# USB_HUB_V1_2.net
KiCad netlist of a schematic drawn in Altium Designer
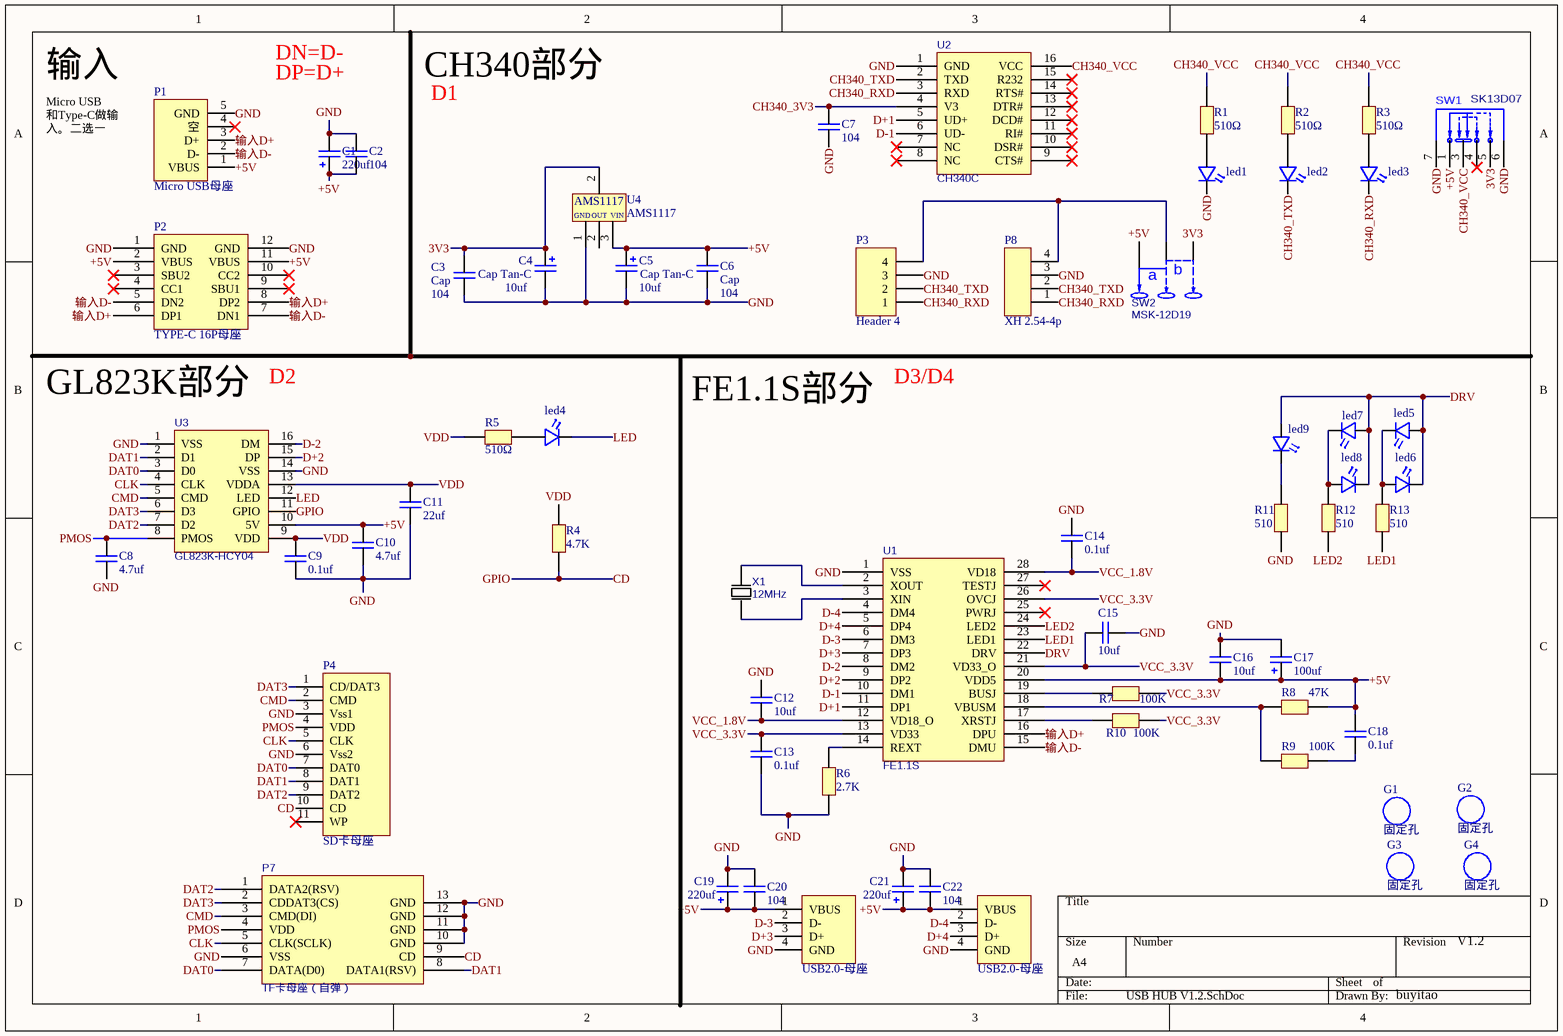
[diagram p0: USB HUB V1.2.SchDoc]

(export (version "E")
  (design (tool "Eeschema 10.0.6"))
  (components
    (comp (ref "C1")
      (value "220uf")
      (footprint "CAP-SMD_BD6.3-L6.6-W6.6-FD")
      (libsource (lib "电容") (part "pcap"))
    )
    (comp (ref "C2") (value "104") (footprint "Cap 0805") (libsource (lib "电容") (part "Cap")))
    (comp (ref "C3")
      (value "Cap")
      (footprint "Cap 0805")
      (fields (field (name "ALTIUM_VALUE") "104"))
      (libsource (lib "电容") (part "Cap"))
    )
    (comp (ref "C4")
      (value "Cap Tan-C")
      (footprint "Cap tan-c")
      (fields (field (name "ALTIUM_VALUE") "10uf"))
      (libsource (lib "电容") (part "Cap Tan-C"))
    )
    (comp (ref "C5")
      (value "Cap Tan-C")
      (footprint "Cap tan-c")
      (fields (field (name "ALTIUM_VALUE") "10uf"))
      (libsource (lib "电容") (part "Cap Tan-C"))
    )
    (comp (ref "C6")
      (value "Cap")
      (footprint "Cap 0805")
      (fields (field (name "ALTIUM_VALUE") "104"))
      (libsource (lib "电容") (part "Cap"))
    )
    (comp (ref "C7") (value "104") (footprint "Cap 0805") (libsource (lib "电容") (part "Cap")))
    (comp (ref "C8") (value "4.7uf") (footprint "Cap 0805") (libsource (lib "电容") (part "Cap")))
    (comp (ref "C9") (value "0.1uf") (footprint "Cap 0805") (libsource (lib "电容") (part "Cap")))
    (comp (ref "C10") (value "4.7uf") (footprint "Cap 0805") (libsource (lib "电容") (part "Cap")))
    (comp (ref "C11") (value "22uf") (footprint "Cap 0805") (libsource (lib "电容") (part "Cap")))
    (comp (ref "C12") (value "10uf") (footprint "Cap 0805") (libsource (lib "电容") (part "Cap")))
    (comp (ref "C13") (value "0.1uf") (footprint "Cap 0805") (libsource (lib "电容") (part "Cap")))
    (comp (ref "C14") (value "0.1uf") (footprint "Cap 0805") (libsource (lib "电容") (part "Cap")))
    (comp (ref "C15") (value "10uf") (footprint "Cap 0805") (libsource (lib "电容") (part "Cap")))
    (comp (ref "C16") (value "10uf") (footprint "Cap 0805") (libsource (lib "电容") (part "Cap")))
    (comp (ref "C17")
      (value "100uf")
      (footprint "CAP-SMD_BD6.3-L6.6-W6.6-FD")
      (libsource (lib "电容") (part "pcap"))
    )
    (comp (ref "C18") (value "0.1uf") (footprint "Cap 0805") (libsource (lib "电容") (part "Cap")))
    (comp (ref "C19")
      (value "220uf")
      (footprint "CAP-SMD_BD6.3-L6.6-W6.6-FD")
      (libsource (lib "电容") (part "pcap"))
    )
    (comp (ref "C20") (value "104") (footprint "Cap 0805") (libsource (lib "电容") (part "Cap")))
    (comp (ref "C21")
      (value "220uf")
      (footprint "CAP-SMD_BD6.3-L6.6-W6.6-FD")
      (libsource (lib "电容") (part "pcap"))
    )
    (comp (ref "C22") (value "104") (footprint "Cap 0805") (libsource (lib "电容") (part "Cap")))
    (comp (ref "G1") (value "固定孔") (footprint "固定孔（M3）") (libsource (lib "其他五金") (part "固定孔")))
    (comp (ref "G2") (value "固定孔") (footprint "固定孔（M3）") (libsource (lib "其他五金") (part "固定孔")))
    (comp (ref "G3") (value "固定孔") (footprint "固定孔（M3）") (libsource (lib "其他五金") (part "固定孔")))
    (comp (ref "G4") (value "固定孔") (footprint "固定孔（M3）") (libsource (lib "其他五金") (part "固定孔")))
    (comp (ref "led1") (value "led") (footprint "led 0805") (libsource (lib "灯") (part "led")))
    (comp (ref "led2") (value "led") (footprint "led 0805") (libsource (lib "灯") (part "led")))
    (comp (ref "led3") (value "led") (footprint "led 0805") (libsource (lib "灯") (part "led")))
    (comp (ref "led4") (value "led") (footprint "led 0805 2号") (libsource (lib "灯") (part "led")))
    (comp (ref "led5") (value "led") (footprint "led 0805 2号") (libsource (lib "灯") (part "led")))
    (comp (ref "led6") (value "led") (footprint "led 0805 2号") (libsource (lib "灯") (part "led")))
    (comp (ref "led7") (value "led") (footprint "led 0805 2号") (libsource (lib "灯") (part "led")))
    (comp (ref "led8") (value "led") (footprint "led 0805 2号") (libsource (lib "灯") (part "led")))
    (comp (ref "led9") (value "led") (footprint "led 0805 2号") (libsource (lib "灯") (part "led")))
    (comp (ref "P1")
      (value "Micro USB母座")
      (footprint "Micro USB母座（沉板0.8带卷边四脚）")
      (libsource (lib "接插件") (part "Micro USB母座"))
    )
    (comp (ref "P2")
      (value "TYPE-C 16P母座")
      (footprint "TYPEC 16P（1.6沉板）")
      (libsource (lib "接插件") (part "TYPE-C 16P母座"))
    )
    (comp (ref "P3")
      (value "Header 4")
      (footprint "HDR1X4")
      (description "Header, 4-Pin")
      (fields (field (name "PUBLISHER") "Altium Limited"))
      (libsource (lib "Miscellaneous Connectors") (part "Header 4"))
    )
    (comp (ref "P4") (value "SD卡母座") (footprint "SD卡母座（短）") (libsource (lib "接插件") (part "SD卡母座")))
    (comp (ref "P5")
      (value "USB2.0-母座")
      (footprint "USB2.0母座弯脚卷边带后盖")
      (libsource (lib "接插件") (part "USB2.0-母座"))
    )
    (comp (ref "P6")
      (value "USB2.0-母座")
      (footprint "USB2.0母座弯脚卷边带后盖")
      (libsource (lib "接插件") (part "USB2.0-母座"))
    )
    (comp (ref "P7")
      (value "TF卡母座（自弹）")
      (footprint "TF卡母座（自弹）")
      (fields (field (name "BOM_MANUFACTURER PART") "TF-01A") (field (name "BOM_SUPPLIER PART") "C91145"))
      (libsource (lib "接插件") (part "TF卡母座（自弹）"))
    )
    (comp (ref "P8")
      (value "XH 2.54-4p")
      (footprint "XH 2.54-4P")
      (libsource (lib "接插件") (part "XH 2.54-4p"))
    )
    (comp (ref "R1") (value "510Ω") (footprint "R 0805") (libsource (lib "电阻") (part "Res")))
    (comp (ref "R2") (value "510Ω") (footprint "R 0805") (libsource (lib "电阻") (part "Res")))
    (comp (ref "R3") (value "510Ω") (footprint "R 0805") (libsource (lib "电阻") (part "Res")))
    (comp (ref "R4") (value "4.7K") (footprint "R 0805") (libsource (lib "电阻") (part "Res")))
    (comp (ref "R5") (value "510Ω") (footprint "R 0805") (libsource (lib "") (part "Res_1")))
    (comp (ref "R6") (value "2.7K") (footprint "R 0805") (libsource (lib "电阻") (part "Res")))
    (comp (ref "R7") (value "100K") (footprint "R 0805") (libsource (lib "") (part "Res_1")))
    (comp (ref "R8") (value "47K") (footprint "R 0805") (libsource (lib "") (part "Res_1")))
    (comp (ref "R9") (value "100K") (footprint "R 0805") (libsource (lib "") (part "Res_1")))
    (comp (ref "R10") (value "100K") (footprint "R 0805") (libsource (lib "") (part "Res_1")))
    (comp (ref "R11") (value "510") (footprint "R 0805") (libsource (lib "电阻") (part "Res")))
    (comp (ref "R12") (value "510") (footprint "R 0805") (libsource (lib "电阻") (part "Res")))
    (comp (ref "R13") (value "510") (footprint "R 0805") (libsource (lib "电阻") (part "Res")))
    (comp (ref "SW1") (value "SK13D07") (footprint "SK13D07") (libsource (lib "开关、按钮") (part "SK13D07")))
    (comp (ref "SW2")
      (value "MSK-12D19")
      (footprint "MSK-12D19")
      (fields
        (field (name "BOM_MANUFACTURER PART") "K3-1260D-L1")
        (field (name "BOM_SUPPLIER PART") "C92657")
      )
      (libsource (lib "开关、按钮") (part "12D19"))
    )
    (comp (ref "U1")
      (value "FE1.1S")
      (footprint "SSOP-28_150MIL")
      (fields (field (name "BOM_SUPPLIER PART") "C9359"))
      (libsource (lib "芯片") (part "FE1.1S"))
    )
    (comp (ref "U2")
      (value "CH340C")
      (footprint "SOP-16_150MIL")
      (fields (field (name "BOM_SUPPLIER PART") "C84681"))
      (libsource (lib "芯片") (part "CH340C"))
    )
    (comp (ref "U3")
      (value "GL823K-HCY04")
      (footprint "SSOP-16_150MIL")
      (fields (field (name "BOM_SUPPLIER PART") "C284879") (field (name "CONTRIBUTOR") "LCSC"))
      (libsource (lib "芯片") (part "GL823K-HCY04"))
    )
    (comp (ref "U4") (value "AMS1117") (footprint "ams1117") (libsource (lib "芯片") (part "AMS1117")))
    (comp (ref "X1")
      (value "12MHz")
      (footprint "HC-49S_L11.4-W4.8")
      (fields
        (field (name "BOM_SUPPLIER PART") "C259040")
        (field (name "BOM_MANUFACTURER PART") "C08000J060")
        (field (name "CONTRIBUTOR") "LCSC")
      )
      (libsource (lib "晶振") (part "8MHz"))
    )
  )
  (nets
    (net (code "1") (name "/+5V") (class "Default")
      (node (ref "C1") (pin "1") (pintype "passive"))
      (node (ref "C10") (pin "1") (pintype "passive"))
      (node (ref "C16") (pin "1") (pintype "passive"))
      (node (ref "C17") (pin "1") (pintype "passive"))
      (node (ref "C18") (pin "2") (pintype "passive"))
      (node (ref "C19") (pin "1") (pintype "passive"))
      (node (ref "C2") (pin "1") (pintype "passive"))
      (node (ref "C20") (pin "1") (pintype "passive"))
      (node (ref "C21") (pin "1") (pintype "passive"))
      (node (ref "C22") (pin "1") (pintype "passive"))
      (node (ref "C5") (pin "1") (pintype "passive"))
      (node (ref "C6") (pin "2") (pintype "passive"))
      (node (ref "P1") (pin "1") (pinfunction "VBUS_1") (pintype "passive"))
      (node (ref "P2") (pin "11") (pinfunction "VBUS_11") (pintype "passive"))
      (node (ref "P2") (pin "2") (pinfunction "VBUS_2") (pintype "passive"))
      (node (ref "P5") (pin "1") (pinfunction "VBUS_1") (pintype "passive"))
      (node (ref "P6") (pin "1") (pinfunction "VBUS_1") (pintype "passive"))
      (node (ref "R8") (pin "2") (pintype "passive"))
      (node (ref "SW1") (pin "1") (pinfunction "1_1") (pintype "passive"))
      (node (ref "SW2") (pin "1") (pinfunction "1_1") (pintype "passive"))
      (node (ref "U1") (pin "20") (pinfunction "VDD5_20") (pintype "passive"))
      (node (ref "U3") (pin "10") (pinfunction "5V_10") (pintype "passive"))
      (node (ref "U4") (pin "3") (pintype "passive"))
    )
    (net (code "2") (name "/3V3") (class "Default")
      (node (ref "C3") (pin "1") (pintype "passive"))
      (node (ref "C4") (pin "1") (pintype "passive"))
      (node (ref "SW1") (pin "5") (pinfunction "5_5") (pintype "passive"))
      (node (ref "SW2") (pin "3") (pinfunction "3_3") (pintype "passive"))
      (node (ref "U4") (pin "2") (pintype "passive"))
    )
    (net (code "3") (name "/CD") (class "Default")
      (node (ref "P4") (pin "10") (pinfunction "CD_10") (pintype "passive"))
      (node (ref "P7") (pin "9") (pinfunction "CD_9") (pintype "passive"))
      (node (ref "R4") (pin "1") (pintype "passive"))
      (node (ref "U3") (pin "11") (pinfunction "GPIO_11") (pintype "passive"))
    )
    (net (code "4") (name "/CH340_3V3") (class "Default")
      (node (ref "C7") (pin "2") (pintype "passive"))
      (node (ref "U2") (pin "4") (pinfunction "V3_4") (pintype "passive"))
    )
    (net (code "5") (name "/CH340_RXD") (class "Default")
      (node (ref "P3") (pin "1") (pinfunction "1_1") (pintype "passive"))
      (node (ref "P8") (pin "1") (pintype "passive"))
      (node (ref "U2") (pin "3") (pinfunction "RXD_3") (pintype "passive"))
      (node (ref "led3") (pin "2") (pintype "passive"))
    )
    (net (code "6") (name "/CH340_TXD") (class "Default")
      (node (ref "P3") (pin "2") (pinfunction "2_2") (pintype "passive"))
      (node (ref "P8") (pin "2") (pintype "passive"))
      (node (ref "U2") (pin "2") (pinfunction "TXD_2") (pintype "passive"))
      (node (ref "led2") (pin "2") (pintype "passive"))
    )
    (net (code "7") (name "/CH340_VCC") (class "Default")
      (node (ref "R1") (pin "2") (pintype "passive"))
      (node (ref "R2") (pin "2") (pintype "passive"))
      (node (ref "R3") (pin "2") (pintype "passive"))
      (node (ref "SW1") (pin "3") (pinfunction "3_3") (pintype "passive"))
      (node (ref "U2") (pin "16") (pinfunction "VCC_16") (pintype "passive"))
    )
    (net (code "8") (name "/CLK") (class "Default")
      (node (ref "P4") (pin "5") (pinfunction "CLK_5") (pintype "passive"))
      (node (ref "P7") (pin "5") (pinfunction "CLK(SCLK)_5") (pintype "passive"))
      (node (ref "U3") (pin "4") (pinfunction "CLK_4") (pintype "passive"))
    )
    (net (code "9") (name "/CMD") (class "Default")
      (node (ref "P4") (pin "2") (pinfunction "CMD_2") (pintype "passive"))
      (node (ref "P7") (pin "3") (pinfunction "CMD(DI)_3") (pintype "passive"))
      (node (ref "U3") (pin "5") (pinfunction "CMD_5") (pintype "passive"))
    )
    (net (code "10") (name "/D+1") (class "Default")
      (node (ref "U1") (pin "11") (pinfunction "DP1_11") (pintype "passive"))
      (node (ref "U2") (pin "5") (pinfunction "UD+_5") (pintype "passive"))
    )
    (net (code "11") (name "/D+2") (class "Default")
      (node (ref "U1") (pin "9") (pinfunction "DP2_9") (pintype "passive"))
      (node (ref "U3") (pin "15") (pinfunction "DP_15") (pintype "passive"))
    )
    (net (code "12") (name "/D+3") (class "Default")
      (node (ref "P5") (pin "3") (pinfunction "D+_3") (pintype "passive"))
      (node (ref "U1") (pin "7") (pinfunction "DP3_7") (pintype "passive"))
    )
    (net (code "13") (name "/D+4") (class "Default")
      (node (ref "P6") (pin "3") (pinfunction "D+_3") (pintype "passive"))
      (node (ref "U1") (pin "5") (pinfunction "DP4_5") (pintype "passive"))
    )
    (net (code "14") (name "/D-1") (class "Default")
      (node (ref "U1") (pin "10") (pinfunction "DM1_10") (pintype "passive"))
      (node (ref "U2") (pin "6") (pinfunction "UD-_6") (pintype "passive"))
    )
    (net (code "15") (name "/D-2") (class "Default")
      (node (ref "U1") (pin "8") (pinfunction "DM2_8") (pintype "passive"))
      (node (ref "U3") (pin "16") (pinfunction "DM_16") (pintype "passive"))
    )
    (net (code "16") (name "/D-3") (class "Default")
      (node (ref "P5") (pin "2") (pinfunction "D-_2") (pintype "passive"))
      (node (ref "U1") (pin "6") (pinfunction "DM3_6") (pintype "passive"))
    )
    (net (code "17") (name "/D-4") (class "Default")
      (node (ref "P6") (pin "2") (pinfunction "D-_2") (pintype "passive"))
      (node (ref "U1") (pin "4") (pinfunction "DM4_4") (pintype "passive"))
    )
    (net (code "18") (name "/DAT0") (class "Default")
      (node (ref "P4") (pin "7") (pinfunction "DAT0_7") (pintype "passive"))
      (node (ref "P7") (pin "7") (pinfunction "DATA(D0)_7") (pintype "passive"))
      (node (ref "U3") (pin "3") (pinfunction "D0_3") (pintype "passive"))
    )
    (net (code "19") (name "/DAT1") (class "Default")
      (node (ref "P4") (pin "8") (pinfunction "DAT1_8") (pintype "passive"))
      (node (ref "P7") (pin "8") (pinfunction "DATA1(RSV)_8") (pintype "passive"))
      (node (ref "U3") (pin "2") (pinfunction "D1_2") (pintype "passive"))
    )
    (net (code "20") (name "/DAT2") (class "Default")
      (node (ref "P4") (pin "9") (pinfunction "DAT2_9") (pintype "passive"))
      (node (ref "P7") (pin "1") (pinfunction "DATA2(RSV)_1") (pintype "passive"))
      (node (ref "U3") (pin "7") (pinfunction "D2_7") (pintype "passive"))
    )
    (net (code "21") (name "/DAT3") (class "Default")
      (node (ref "P4") (pin "1") (pinfunction "CD/DAT3_1") (pintype "passive"))
      (node (ref "P7") (pin "2") (pinfunction "CDDAT3(CS)_2") (pintype "passive"))
      (node (ref "U3") (pin "6") (pinfunction "D3_6") (pintype "passive"))
    )
    (net (code "22") (name "/DRV") (class "Default")
      (node (ref "U1") (pin "22") (pinfunction "DRV_22") (pintype "passive"))
      (node (ref "led5") (pin "1") (pintype "passive"))
      (node (ref "led6") (pin "2") (pintype "passive"))
      (node (ref "led7") (pin "1") (pintype "passive"))
      (node (ref "led8") (pin "2") (pintype "passive"))
      (node (ref "led9") (pin "1") (pintype "passive"))
    )
    (net (code "23") (name "/GND") (class "Default")
      (node (ref "C1") (pin "2") (pintype "passive"))
      (node (ref "C10") (pin "2") (pintype "passive"))
      (node (ref "C11") (pin "2") (pintype "passive"))
      (node (ref "C12") (pin "1") (pintype "passive"))
      (node (ref "C13") (pin "2") (pintype "passive"))
      (node (ref "C14") (pin "2") (pintype "passive"))
      (node (ref "C15") (pin "2") (pintype "passive"))
      (node (ref "C16") (pin "2") (pintype "passive"))
      (node (ref "C17") (pin "2") (pintype "passive"))
      (node (ref "C19") (pin "2") (pintype "passive"))
      (node (ref "C2") (pin "2") (pintype "passive"))
      (node (ref "C20") (pin "2") (pintype "passive"))
      (node (ref "C21") (pin "2") (pintype "passive"))
      (node (ref "C22") (pin "2") (pintype "passive"))
      (node (ref "C3") (pin "2") (pintype "passive"))
      (node (ref "C4") (pin "2") (pintype "passive"))
      (node (ref "C5") (pin "2") (pintype "passive"))
      (node (ref "C6") (pin "1") (pintype "passive"))
      (node (ref "C7") (pin "1") (pintype "passive"))
      (node (ref "C8") (pin "2") (pintype "passive"))
      (node (ref "C9") (pin "2") (pintype "passive"))
      (node (ref "P1") (pin "5") (pinfunction "GND_5") (pintype "passive"))
      (node (ref "P2") (pin "1") (pinfunction "GND_1") (pintype "passive"))
      (node (ref "P2") (pin "12") (pinfunction "GND_12") (pintype "passive"))
      (node (ref "P3") (pin "3") (pinfunction "3_3") (pintype "passive"))
      (node (ref "P4") (pin "3") (pinfunction "Vss1_3") (pintype "passive"))
      (node (ref "P4") (pin "6") (pinfunction "Vss2_6") (pintype "passive"))
      (node (ref "P5") (pin "4") (pinfunction "GND_4") (pintype "passive"))
      (node (ref "P6") (pin "4") (pinfunction "GND_4") (pintype "passive"))
      (node (ref "P7") (pin "10") (pinfunction "GND_10") (pintype "passive"))
      (node (ref "P7") (pin "11") (pinfunction "GND_11") (pintype "passive"))
      (node (ref "P7") (pin "12") (pinfunction "GND_12") (pintype "passive"))
      (node (ref "P7") (pin "13") (pinfunction "GND_13") (pintype "passive"))
      (node (ref "P7") (pin "6") (pinfunction "VSS_6") (pintype "passive"))
      (node (ref "P8") (pin "3") (pintype "passive"))
      (node (ref "R11") (pin "1") (pintype "passive"))
      (node (ref "R6") (pin "1") (pintype "passive"))
      (node (ref "SW1") (pin "6") (pinfunction "6_6") (pintype "passive"))
      (node (ref "SW1") (pin "7") (pinfunction "7_7") (pintype "passive"))
      (node (ref "U1") (pin "1") (pinfunction "VSS_1") (pintype "passive"))
      (node (ref "U2") (pin "1") (pinfunction "GND_1") (pintype "passive"))
      (node (ref "U3") (pin "1") (pinfunction "VSS_1") (pintype "passive"))
      (node (ref "U3") (pin "14") (pinfunction "VSS_14") (pintype "passive"))
      (node (ref "U4") (pin "1") (pintype "passive"))
      (node (ref "led1") (pin "2") (pintype "passive"))
    )
    (net (code "24") (name "/LED") (class "Default")
      (node (ref "U3") (pin "12") (pinfunction "LED_12") (pintype "passive"))
      (node (ref "led4") (pin "2") (pintype "passive"))
    )
    (net (code "25") (name "/LED1") (class "Default")
      (node (ref "R13") (pin "1") (pintype "passive"))
      (node (ref "U1") (pin "23") (pinfunction "LED1_23") (pintype "passive"))
    )
    (net (code "26") (name "/LED2") (class "Default")
      (node (ref "R12") (pin "1") (pintype "passive"))
      (node (ref "U1") (pin "24") (pinfunction "LED2_24") (pintype "passive"))
    )
    (net (code "27") (name "/PMOS") (class "Default")
      (node (ref "C8") (pin "1") (pintype "passive"))
      (node (ref "P4") (pin "4") (pinfunction "VDD_4") (pintype "passive"))
      (node (ref "P7") (pin "4") (pinfunction "VDD_4") (pintype "passive"))
      (node (ref "U3") (pin "8") (pinfunction "PMOS_8") (pintype "passive"))
    )
    (net (code "28") (name "/VCC_1.8V") (class "Default")
      (node (ref "C12") (pin "2") (pintype "passive"))
      (node (ref "C14") (pin "1") (pintype "passive"))
      (node (ref "U1") (pin "12") (pinfunction "VD18_O_12") (pintype "passive"))
      (node (ref "U1") (pin "28") (pinfunction "VD18_28") (pintype "passive"))
    )
    (net (code "29") (name "/VCC_3.3V") (class "Default")
      (node (ref "C13") (pin "1") (pintype "passive"))
      (node (ref "C15") (pin "1") (pintype "passive"))
      (node (ref "R10") (pin "2") (pintype "passive"))
      (node (ref "R7") (pin "2") (pintype "passive"))
      (node (ref "U1") (pin "13") (pinfunction "VD33_13") (pintype "passive"))
      (node (ref "U1") (pin "21") (pinfunction "VD33_O_21") (pintype "passive"))
      (node (ref "U1") (pin "26") (pinfunction "OVCJ_26") (pintype "passive"))
    )
    (net (code "30") (name "/VDD") (class "Default")
      (node (ref "C11") (pin "1") (pintype "passive"))
      (node (ref "C9") (pin "1") (pintype "passive"))
      (node (ref "R4") (pin "2") (pintype "passive"))
      (node (ref "R5") (pin "1") (pintype "passive"))
      (node (ref "U3") (pin "13") (pinfunction "VDDA_13") (pintype "passive"))
      (node (ref "U3") (pin "9") (pinfunction "VDD_9") (pintype "passive"))
    )
    (net (code "31") (name "/输入D+") (class "Default")
      (node (ref "P1") (pin "3") (pinfunction "D+_3") (pintype "passive"))
      (node (ref "P2") (pin "6") (pinfunction "DP1_6") (pintype "passive"))
      (node (ref "P2") (pin "8") (pinfunction "DP2_8") (pintype "passive"))
      (node (ref "U1") (pin "16") (pinfunction "DPU_16") (pintype "passive"))
    )
    (net (code "32") (name "/输入D-") (class "Default")
      (node (ref "P1") (pin "2") (pinfunction "D-_2") (pintype "passive"))
      (node (ref "P2") (pin "5") (pinfunction "DN2_5") (pintype "passive"))
      (node (ref "P2") (pin "7") (pinfunction "DN1_7") (pintype "passive"))
      (node (ref "U1") (pin "15") (pinfunction "DMU_15") (pintype "passive"))
    )
    (net (code "33") (name "Net-(C18-Pad1)") (class "Default")
      (node (ref "C18") (pin "1") (pintype "passive"))
      (node (ref "R9") (pin "2") (pintype "passive"))
    )
    (net (code "34") (name "Net-(P3-Pad4)") (class "Default")
      (node (ref "P3") (pin "4") (pinfunction "4_4") (pintype "passive"))
      (node (ref "P8") (pin "4") (pintype "passive"))
      (node (ref "SW2") (pin "2") (pinfunction "2_2") (pintype "passive"))
    )
    (net (code "35") (name "Net-(R1-Pad1)") (class "Default")
      (node (ref "R1") (pin "1") (pintype "passive"))
      (node (ref "led1") (pin "1") (pintype "passive"))
    )
    (net (code "36") (name "Net-(R2-Pad1)") (class "Default")
      (node (ref "R2") (pin "1") (pintype "passive"))
      (node (ref "led2") (pin "1") (pintype "passive"))
    )
    (net (code "37") (name "Net-(R3-Pad1)") (class "Default")
      (node (ref "R3") (pin "1") (pintype "passive"))
      (node (ref "led3") (pin "1") (pintype "passive"))
    )
    (net (code "38") (name "Net-(R5-Pad2)") (class "Default")
      (node (ref "R5") (pin "2") (pintype "passive"))
      (node (ref "led4") (pin "1") (pintype "passive"))
    )
    (net (code "39") (name "Net-(R11-Pad2)") (class "Default")
      (node (ref "R11") (pin "2") (pintype "passive"))
      (node (ref "led9") (pin "2") (pintype "passive"))
    )
    (net (code "40") (name "Net-(R12-Pad2)") (class "Default")
      (node (ref "R12") (pin "2") (pintype "passive"))
      (node (ref "led7") (pin "2") (pintype "passive"))
      (node (ref "led8") (pin "1") (pintype "passive"))
    )
    (net (code "41") (name "Net-(R13-Pad2)") (class "Default")
      (node (ref "R13") (pin "2") (pintype "passive"))
      (node (ref "led5") (pin "2") (pintype "passive"))
      (node (ref "led6") (pin "1") (pintype "passive"))
    )
    (net (code "42") (name "Net-(U1-BUSJ)") (class "Default")
      (node (ref "R7") (pin "1") (pintype "passive"))
      (node (ref "U1") (pin "19") (pinfunction "BUSJ_19") (pintype "passive"))
    )
    (net (code "43") (name "Net-(U1-REXT)") (class "Default")
      (node (ref "R6") (pin "2") (pintype "passive"))
      (node (ref "U1") (pin "14") (pinfunction "REXT_14") (pintype "passive"))
    )
    (net (code "44") (name "Net-(U1-VBUSM)") (class "Default")
      (node (ref "R8") (pin "1") (pintype "passive"))
      (node (ref "R9") (pin "1") (pintype "passive"))
      (node (ref "U1") (pin "18") (pinfunction "VBUSM_18") (pintype "passive"))
    )
    (net (code "45") (name "Net-(U1-XIN)") (class "Default")
      (node (ref "U1") (pin "3") (pinfunction "XIN_3") (pintype "passive"))
      (node (ref "X1") (pin "1") (pinfunction "OSC1_1") (pintype "passive"))
    )
    (net (code "46") (name "Net-(U1-XOUT)") (class "Default")
      (node (ref "U1") (pin "2") (pinfunction "XOUT_2") (pintype "passive"))
      (node (ref "X1") (pin "2") (pinfunction "OSC2_2") (pintype "passive"))
    )
    (net (code "47") (name "Net-(U1-XRSTJ)") (class "Default")
      (node (ref "R10") (pin "1") (pintype "passive"))
      (node (ref "U1") (pin "17") (pinfunction "XRSTJ_17") (pintype "passive"))
    )
    (net (code "48") (name "unconnected-(P1-空-Pad4)") (class "Default")
      (node (ref "P1") (pin "4") (pinfunction "空_4") (pintype "passive+no_connect"))
    )
    (net (code "49") (name "unconnected-(P2-CC1-Pad4)") (class "Default")
      (node (ref "P2") (pin "4") (pinfunction "CC1_4") (pintype "passive+no_connect"))
    )
    (net (code "50") (name "unconnected-(P2-CC2-Pad10)") (class "Default")
      (node (ref "P2") (pin "10") (pinfunction "CC2_10") (pintype "passive+no_connect"))
    )
    (net (code "51") (name "unconnected-(P2-SBU1-Pad9)") (class "Default")
      (node (ref "P2") (pin "9") (pinfunction "SBU1_9") (pintype "passive+no_connect"))
    )
    (net (code "52") (name "unconnected-(P2-SBU2-Pad3)") (class "Default")
      (node (ref "P2") (pin "3") (pinfunction "SBU2_3") (pintype "passive+no_connect"))
    )
    (net (code "53") (name "unconnected-(P4-WP-Pad11)") (class "Default")
      (node (ref "P4") (pin "11") (pinfunction "WP_11") (pintype "passive+no_connect"))
    )
    (net (code "54") (name "unconnected-(SW1-Pad4)") (class "Default")
      (node (ref "SW1") (pin "4") (pinfunction "4_4") (pintype "passive+no_connect"))
    )
    (net (code "55") (name "unconnected-(U1-PWRJ-Pad25)") (class "Default")
      (node (ref "U1") (pin "25") (pinfunction "PWRJ_25") (pintype "passive+no_connect"))
    )
    (net (code "56") (name "unconnected-(U1-TESTJ-Pad27)") (class "Default")
      (node (ref "U1") (pin "27") (pinfunction "TESTJ_27") (pintype "passive+no_connect"))
    )
    (net (code "57") (name "unconnected-(U2-CTS#-Pad9)") (class "Default")
      (node (ref "U2") (pin "9") (pinfunction "CTS#_9") (pintype "passive+no_connect"))
    )
    (net (code "58") (name "unconnected-(U2-DCD#-Pad12)") (class "Default")
      (node (ref "U2") (pin "12") (pinfunction "DCD#_12") (pintype "passive+no_connect"))
    )
    (net (code "59") (name "unconnected-(U2-DSR#-Pad10)") (class "Default")
      (node (ref "U2") (pin "10") (pinfunction "DSR#_10") (pintype "passive+no_connect"))
    )
    (net (code "60") (name "unconnected-(U2-DTR#-Pad13)") (class "Default")
      (node (ref "U2") (pin "13") (pinfunction "DTR#_13") (pintype "passive+no_connect"))
    )
    (net (code "61") (name "unconnected-(U2-NC-Pad7)") (class "Default")
      (node (ref "U2") (pin "7") (pinfunction "NC_7") (pintype "passive+no_connect"))
    )
    (net (code "62") (name "unconnected-(U2-NC-Pad8)") (class "Default")
      (node (ref "U2") (pin "8") (pinfunction "NC_8") (pintype "passive+no_connect"))
    )
    (net (code "63") (name "unconnected-(U2-R232-Pad15)") (class "Default")
      (node (ref "U2") (pin "15") (pinfunction "R232_15") (pintype "passive+no_connect"))
    )
    (net (code "64") (name "unconnected-(U2-RI#-Pad11)") (class "Default")
      (node (ref "U2") (pin "11") (pinfunction "RI#_11") (pintype "passive+no_connect"))
    )
    (net (code "65") (name "unconnected-(U2-RTS#-Pad14)") (class "Default")
      (node (ref "U2") (pin "14") (pinfunction "RTS#_14") (pintype "passive+no_connect"))
    )
    (net (code "66") (name "unconnected-(U4-Pad2)") (class "Default")
      (node (ref "U4") (pin "2") (pintype "passive"))
    )
  )
)
